# PG10__MCU.net
KiCad netlist of a schematic drawn in Altium Designer
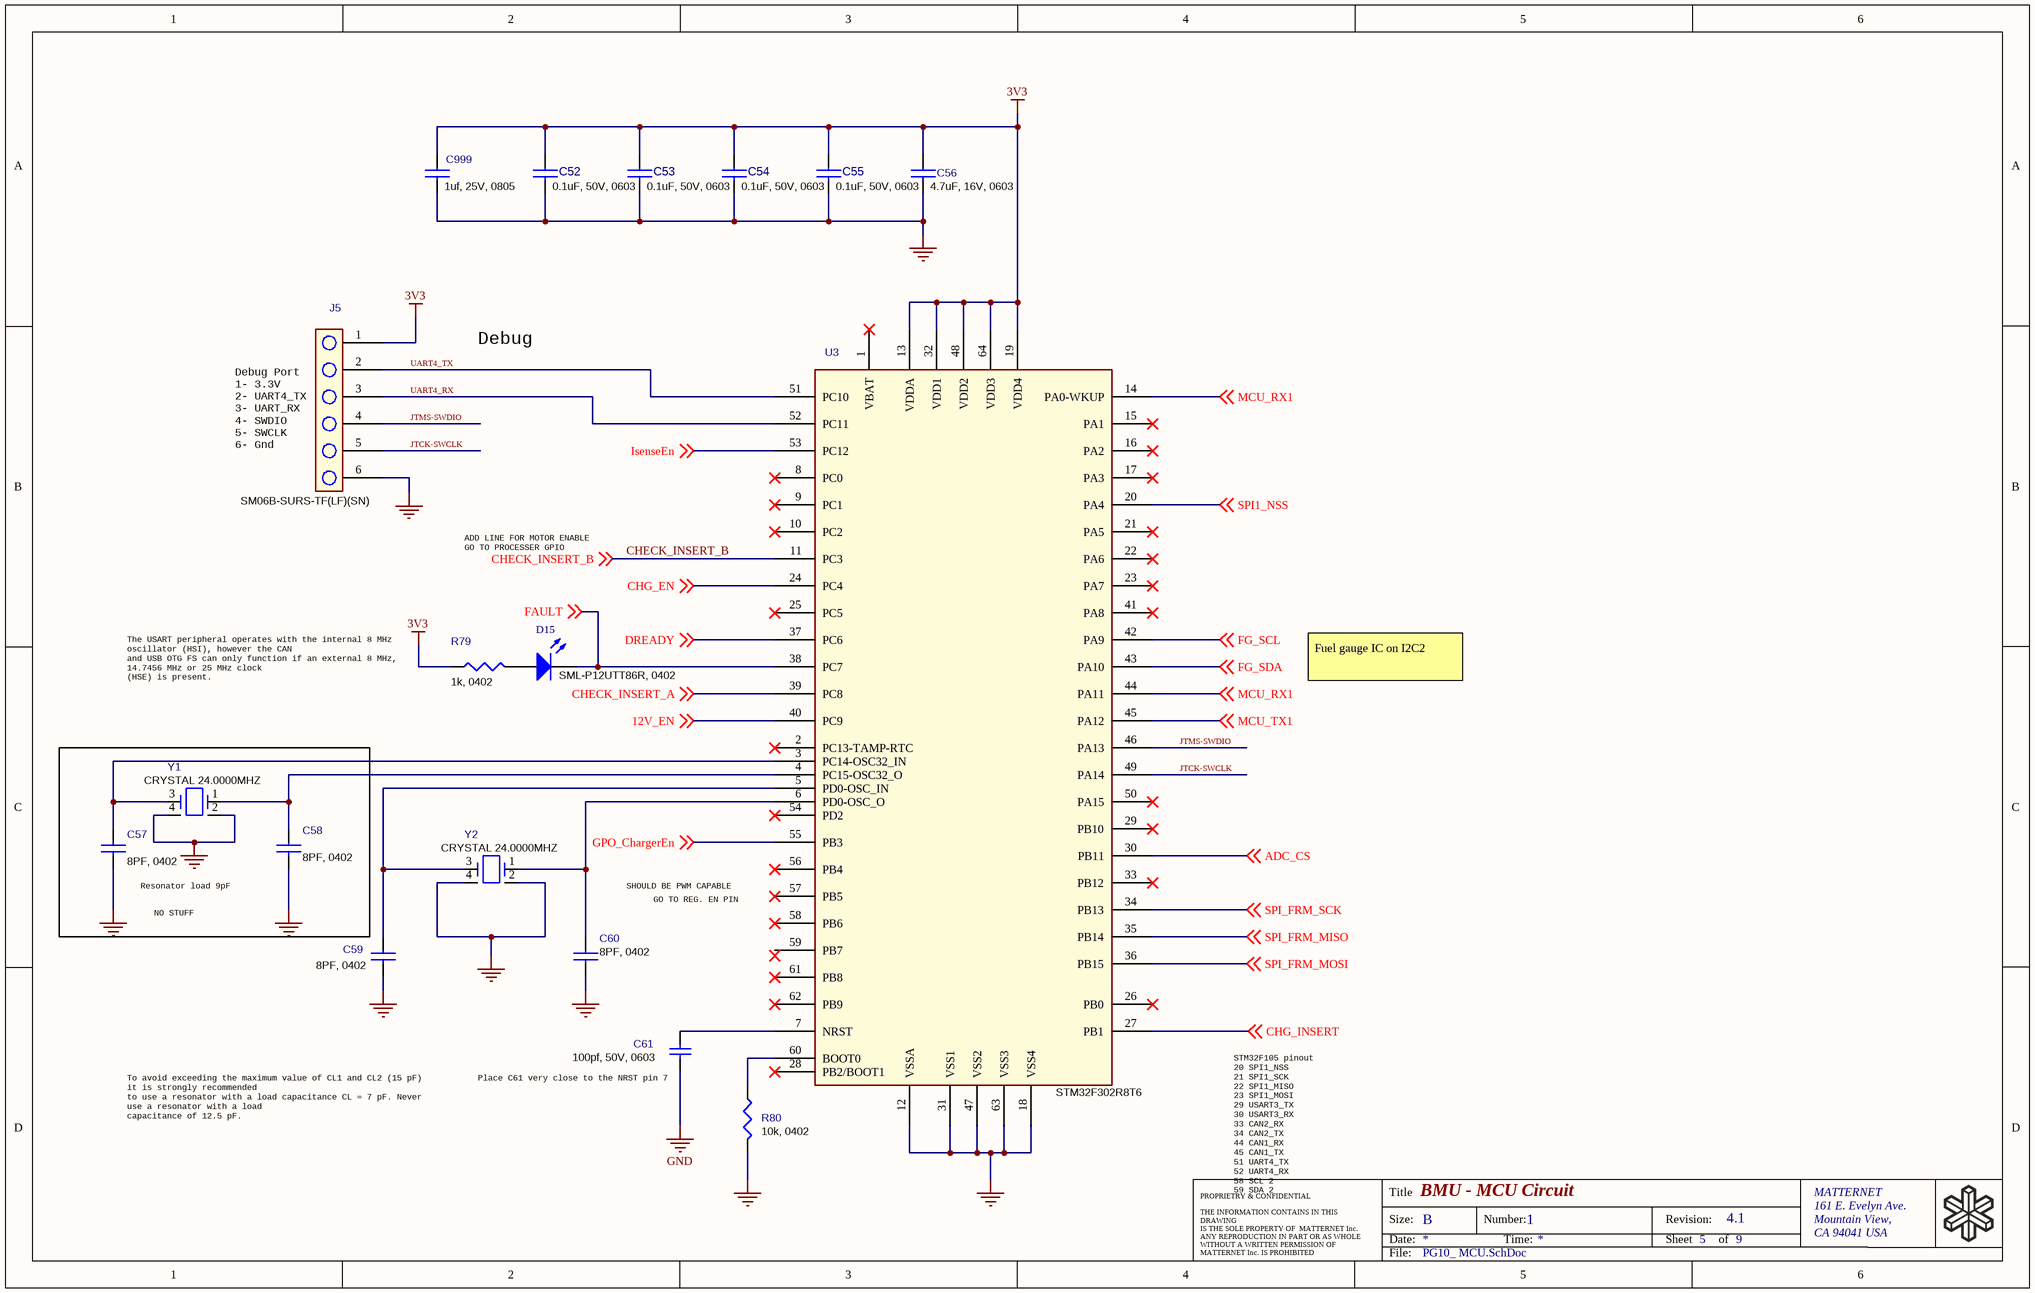
[diagram p0: PG10_ MCU.SchDoc]

(export (version "E")
  (design (tool "Eeschema 10.0.6"))
  (components
    (comp (ref "C52")
      (value "0.1uF, 50V, 0603")
      (footprint "C0603")
      (description "CAP CER 0.1UF 50V 10% X7R 0603")
      (fields
        (field (name "MANUFACTURER") "Murata")
        (field (name "MANUFACTURER PART NUMBER") "GCJ188R71E104KA12D")
      )
      (libsource (lib "*") (part "CAP-Generic-0603"))
    )
    (comp (ref "C53")
      (value "0.1uF, 50V, 0603")
      (footprint "C0603")
      (description "CAP CER 0.1UF 50V 10% X7R 0603")
      (fields
        (field (name "MANUFACTURER") "Murata")
        (field (name "MANUFACTURER PART NUMBER") "GCJ188R71E104KA12D")
      )
      (libsource (lib "*") (part "CAP-Generic-0603"))
    )
    (comp (ref "C54")
      (value "0.1uF, 50V, 0603")
      (footprint "C0603")
      (description "CAP CER 0.1UF 50V 10% X7R 0603")
      (fields
        (field (name "MANUFACTURER") "Murata")
        (field (name "MANUFACTURER PART NUMBER") "GCJ188R71E104KA12D")
      )
      (libsource (lib "*") (part "CAP-Generic-0603"))
    )
    (comp (ref "C55")
      (value "0.1uF, 50V, 0603")
      (footprint "C0603")
      (description "CAP CER 0.1UF 50V 10% X7R 0603")
      (fields
        (field (name "MANUFACTURER") "Murata")
        (field (name "MANUFACTURER PART NUMBER") "GCJ188R71E104KA12D")
      )
      (libsource (lib "*") (part "CAP-Generic-0603"))
    )
    (comp (ref "C56")
      (value "4.7uF, 16V, 0603")
      (footprint "C0805")
      (description "CAP CER 4.7UF 16V 10% X7R 0805")
      (fields
        (field (name "MANUFACTURER") "TDK")
        (field (name "MANUFACTURER PART NUMBER") "CGA4J3X7R1C475K125AE")
      )
      (libsource (lib "*") (part "CAP-Generic-0603"))
    )
    (comp (ref "C57")
      (value "8PF, 0402")
      (footprint "C0402")
      (description "CAP CER 8PF 50V C0G 0402")
      (fields
        (field (name "MANUFACTURER") "TDK")
        (field (name "MANUFACTURER PART NUMBER") "CGA2B2C0G1H080D050BA")
      )
      (libsource (lib "*") (part "CAP-Generic-0402"))
    )
    (comp (ref "C58")
      (value "8PF, 0402")
      (footprint "C0402")
      (description "CAP CER 8PF 50V C0G 0402")
      (fields
        (field (name "MANUFACTURER") "TDK")
        (field (name "MANUFACTURER PART NUMBER") "CGA2B2C0G1H080D050BA")
      )
      (libsource (lib "*") (part "CAP-Generic-0402"))
    )
    (comp (ref "C59")
      (value "8PF, 0402")
      (footprint "C0402")
      (description "CAP CER 8PF 50V C0G 0402")
      (fields
        (field (name "MANUFACTURER") "TDK")
        (field (name "MANUFACTURER PART NUMBER") "CGA2B2C0G1H080D050BA")
      )
      (libsource (lib "*") (part "CAP-Generic-0402"))
    )
    (comp (ref "C60")
      (value "8PF, 0402")
      (footprint "C0402")
      (description "CAP CER 8PF 50V C0G 0402")
      (fields
        (field (name "MANUFACTURER") "TDK")
        (field (name "MANUFACTURER PART NUMBER") "CGA2B2C0G1H080D050BA")
      )
      (libsource (lib "*") (part "CAP-Generic-0402"))
    )
    (comp (ref "C61")
      (value "100pf, 50V, 0603")
      (footprint "C0603")
      (description "CAP CER 100PF 50V NP0 0603")
      (fields
        (field (name "MANUFACTURER") "TDK")
        (field (name "MANUFACTURER PART NUMBER") "CGA3E2C0G1H101J080AE")
      )
      (libsource (lib "Miscellaneous Devices") (part "Cap"))
    )
    (comp (ref "C999")
      (value "1uf, 25V, 0805")
      (footprint "C0805")
      (description "CAP CER 1UF 25V X7R 0805")
      (fields
        (field (name "MANUFACTURER") "Murata")
        (field (name "MANUFACTURER PART NUMBER") "GCJ21BR71E105KA12L")
      )
      (libsource (lib "*") (part "CAP-Generic-0402"))
    )
    (comp (ref "D15")
      (value "SML-P12UTT86R, 0402")
      (footprint "D0402_1")
      (description "LED Uni-Color Red Chip LED 2-Pin 0402 T/R")
      (fields (field (name "MANUFACTURER") "Rohm") (field (name "MANUFACTURER PART NUMBER") "SML-P12U2TT86R"))
      (libsource (lib "Miscellaneous Devices") (part "LED0"))
    )
    (comp (ref "J5")
      (value "SM06B-SURS-TF(LF)(SN)")
      (footprint "0.8mm")
      (description "Headers & Wire Housings 6P SR UNSHRD HRD TIN OVER NI")
      (fields (field (name "MANUFACTURER") "JST"))
      (libsource (lib "*") (part "CONN-GENERIC-1X6"))
    )
    (comp (ref "R79")
      (value "1k, 0402")
      (footprint "R0402")
      (description "RES SMD 1K OHM 5% 1/16W 0402")
      (fields
        (field (name "MANUFACTURER") "Yageo")
        (field (name "MANUFACTURER PART NUMBER") "RC0402JR-071KL")
      )
      (libsource (lib "*") (part "R-Generic-0402"))
    )
    (comp (ref "R80")
      (value "10k, 0402")
      (footprint "R0402")
      (description "RES SMD 10K OHM 1% 1/16W 0402")
      (fields
        (field (name "MANUFACTURER") "Vishay Dale")
        (field (name "MANUFACTURER PART NUMBER") "CRCW040210K0FKTD")
      )
      (libsource (lib "Miscellaneous Devices") (part "R-Generic-0402"))
    )
    (comp (ref "U3")
      (value "STM32F302R8T6")
      (footprint "64LQFP")
      (description "MCU 32-bit STM32 ARM Cortex M4 RISC 128KB Flash 2.5V/3.3V 64-Pin LQFP Tray")
      (libsource (lib "*") (part "MCU-STM32F105RBT6-700-443"))
    )
    (comp (ref "Y1")
      (value "CRYSTAL 24.0000MHZ")
      (footprint "CRYSTAL_NX3225SA")
      (description "CRYSTAL 24.0000MHZ 8PF SMD")
      (fields
        (field (name "MANUFACTURER") "NDK")
        (field (name "MANUFACTURER PART NUMBER") "NX3225SA-24.000MHZ-STD-CSR-1")
      )
      (libsource (lib "*") (part "CRY-Generic"))
    )
    (comp (ref "Y2")
      (value "CRYSTAL 24.0000MHZ")
      (footprint "CRYSTAL_NX3225SA")
      (description "CRYSTAL 24.0000MHZ 8PF SMD")
      (fields
        (field (name "MANUFACTURER") "NDK")
        (field (name "MANUFACTURER PART NUMBER") "NX3225SA-24.000MHZ-STD-CSR-1")
      )
      (libsource (lib "*") (part "CRY-Generic"))
    )
  )
  (nets
    (net (code "1") (name "/JTCK-SWCLK") (class "Default")
      (node (ref "J5") (pin "5") (pinfunction "5_5") (pintype "passive"))
      (node (ref "U3") (pin "49") (pinfunction "PA14_49") (pintype "passive"))
    )
    (net (code "2") (name "/JTMS-SWDIO") (class "Default")
      (node (ref "J5") (pin "4") (pinfunction "4_4") (pintype "passive"))
      (node (ref "U3") (pin "46") (pinfunction "PA13_46") (pintype "passive"))
    )
    (net (code "3") (name "/UART4_RX") (class "Default")
      (node (ref "J5") (pin "3") (pinfunction "3_3") (pintype "passive"))
      (node (ref "U3") (pin "52") (pinfunction "PC11_52") (pintype "passive"))
    )
    (net (code "4") (name "/UART4_TX") (class "Default")
      (node (ref "J5") (pin "2") (pinfunction "2_2") (pintype "passive"))
      (node (ref "U3") (pin "51") (pinfunction "PC10_51") (pintype "passive"))
    )
    (net (code "5") (name "3V3") (class "Default")
      (node (ref "C52") (pin "1") (pinfunction "1_1") (pintype "passive"))
      (node (ref "C53") (pin "1") (pinfunction "1_1") (pintype "passive"))
      (node (ref "C54") (pin "1") (pinfunction "1_1") (pintype "passive"))
      (node (ref "C55") (pin "1") (pinfunction "1_1") (pintype "passive"))
      (node (ref "C56") (pin "1") (pinfunction "1_1") (pintype "passive"))
      (node (ref "C999") (pin "1") (pinfunction "1_1") (pintype "passive"))
      (node (ref "J5") (pin "1") (pinfunction "1_1") (pintype "passive"))
      (node (ref "R79") (pin "1") (pinfunction "1_1") (pintype "passive"))
      (node (ref "U3") (pin "13") (pinfunction "VDDA_13") (pintype "passive"))
      (node (ref "U3") (pin "19") (pinfunction "VDD4_19") (pintype "passive"))
      (node (ref "U3") (pin "32") (pinfunction "VDD1_32") (pintype "passive"))
      (node (ref "U3") (pin "48") (pinfunction "VDD2_48") (pintype "passive"))
      (node (ref "U3") (pin "64") (pinfunction "VDD3_64") (pintype "passive"))
    )
    (net (code "6") (name "12V_EN") (class "Default")
      (node (ref "U3") (pin "40") (pinfunction "PC9_40") (pintype "passive"))
    )
    (net (code "7") (name "ADC_CS") (class "Default")
      (node (ref "U3") (pin "30") (pinfunction "PB11_30") (pintype "passive"))
    )
    (net (code "8") (name "CHECK_INSERT_A") (class "Default")
      (node (ref "U3") (pin "39") (pinfunction "PC8_39") (pintype "passive"))
    )
    (net (code "9") (name "CHECK_INSERT_B") (class "Default")
      (node (ref "U3") (pin "11") (pinfunction "PC3_11") (pintype "passive"))
    )
    (net (code "10") (name "CHG_EN") (class "Default")
      (node (ref "U3") (pin "24") (pinfunction "PC4_24") (pintype "passive"))
    )
    (net (code "11") (name "CHG_INSERT") (class "Default")
      (node (ref "U3") (pin "27") (pinfunction "PB1_27") (pintype "passive"))
    )
    (net (code "12") (name "DREADY") (class "Default")
      (node (ref "U3") (pin "37") (pinfunction "PC6_37") (pintype "passive"))
    )
    (net (code "13") (name "FAULT") (class "Default")
      (node (ref "D15") (pin "2") (pinfunction "K_2") (pintype "passive"))
      (node (ref "U3") (pin "38") (pinfunction "PC7_38") (pintype "passive"))
    )
    (net (code "14") (name "FG_SCL") (class "Default")
      (node (ref "U3") (pin "42") (pinfunction "PA9_42") (pintype "passive"))
    )
    (net (code "15") (name "FG_SDA") (class "Default")
      (node (ref "U3") (pin "43") (pinfunction "PA10_43") (pintype "passive"))
    )
    (net (code "16") (name "GND") (class "Default")
      (node (ref "C52") (pin "2") (pinfunction "2_2") (pintype "passive"))
      (node (ref "C53") (pin "2") (pinfunction "2_2") (pintype "passive"))
      (node (ref "C54") (pin "2") (pinfunction "2_2") (pintype "passive"))
      (node (ref "C55") (pin "2") (pinfunction "2_2") (pintype "passive"))
      (node (ref "C56") (pin "2") (pinfunction "2_2") (pintype "passive"))
      (node (ref "C57") (pin "2") (pinfunction "2_2") (pintype "passive"))
      (node (ref "C58") (pin "2") (pinfunction "2_2") (pintype "passive"))
      (node (ref "C59") (pin "2") (pinfunction "2_2") (pintype "passive"))
      (node (ref "C60") (pin "2") (pinfunction "2_2") (pintype "passive"))
      (node (ref "C61") (pin "1") (pinfunction "1_1") (pintype "passive"))
      (node (ref "C999") (pin "2") (pinfunction "2_2") (pintype "passive"))
      (node (ref "J5") (pin "6") (pinfunction "6_6") (pintype "passive"))
      (node (ref "R80") (pin "2") (pinfunction "2_2") (pintype "passive"))
      (node (ref "U3") (pin "12") (pinfunction "VSSA_12") (pintype "passive"))
      (node (ref "U3") (pin "18") (pinfunction "VSS4_18") (pintype "passive"))
      (node (ref "U3") (pin "31") (pinfunction "VSS1_31") (pintype "passive"))
      (node (ref "U3") (pin "47") (pinfunction "VSS2_47") (pintype "passive"))
      (node (ref "U3") (pin "63") (pinfunction "VSS3_63") (pintype "passive"))
      (node (ref "Y1") (pin "2") (pinfunction "2_2") (pintype "passive"))
      (node (ref "Y1") (pin "4") (pinfunction "4_4") (pintype "passive"))
      (node (ref "Y2") (pin "2") (pinfunction "2_2") (pintype "passive"))
      (node (ref "Y2") (pin "4") (pinfunction "4_4") (pintype "passive"))
    )
    (net (code "17") (name "GPO_ChargerEn") (class "Default")
      (node (ref "U3") (pin "55") (pinfunction "PB3_55") (pintype "passive"))
    )
    (net (code "18") (name "IsenseEn") (class "Default")
      (node (ref "U3") (pin "53") (pinfunction "PC12_53") (pintype "passive"))
    )
    (net (code "19") (name "MCU_RX1") (class "Default")
      (node (ref "U3") (pin "14") (pinfunction "PA0-WKUP_14") (pintype "passive"))
      (node (ref "U3") (pin "44") (pinfunction "PA11_44") (pintype "passive"))
    )
    (net (code "20") (name "MCU_TX1") (class "Default")
      (node (ref "U3") (pin "45") (pinfunction "PA12_45") (pintype "passive"))
    )
    (net (code "21") (name "Net-(U3-BOOT0)") (class "Default")
      (node (ref "R80") (pin "1") (pinfunction "1_1") (pintype "passive"))
      (node (ref "U3") (pin "60") (pinfunction "BOOT0_60") (pintype "passive"))
    )
    (net (code "22") (name "Net-(U3-NRST)") (class "Default")
      (node (ref "C61") (pin "2") (pinfunction "2_2") (pintype "passive"))
      (node (ref "U3") (pin "7") (pinfunction "NRST_7") (pintype "passive"))
    )
    (net (code "23") (name "Net-(U3-PC14-OSC32_IN)") (class "Default")
      (node (ref "C57") (pin "1") (pinfunction "1_1") (pintype "passive"))
      (node (ref "U3") (pin "3") (pinfunction "PC14-OSC32_IN_3") (pintype "passive"))
      (node (ref "Y1") (pin "3") (pinfunction "3_3") (pintype "passive"))
    )
    (net (code "24") (name "Net-(U3-PC15-OSC32_O)") (class "Default")
      (node (ref "C58") (pin "1") (pinfunction "1_1") (pintype "passive"))
      (node (ref "U3") (pin "4") (pinfunction "PC15-OSC32_O_4") (pintype "passive"))
      (node (ref "Y1") (pin "1") (pinfunction "1_1") (pintype "passive"))
    )
    (net (code "25") (name "Net-(U3-PD0-OSC_IN)") (class "Default")
      (node (ref "C59") (pin "1") (pinfunction "1_1") (pintype "passive"))
      (node (ref "U3") (pin "5") (pinfunction "PD0-OSC_IN_5") (pintype "passive"))
      (node (ref "Y2") (pin "3") (pinfunction "3_3") (pintype "passive"))
    )
    (net (code "26") (name "Net-(U3-PD0-OSC_O)") (class "Default")
      (node (ref "C60") (pin "1") (pinfunction "1_1") (pintype "passive"))
      (node (ref "U3") (pin "6") (pinfunction "PD0-OSC_O_6") (pintype "passive"))
      (node (ref "Y2") (pin "1") (pinfunction "1_1") (pintype "passive"))
    )
    (net (code "27") (name "SPI1_NSS") (class "Default")
      (node (ref "U3") (pin "20") (pinfunction "PA4_20") (pintype "passive"))
    )
    (net (code "28") (name "SPI_FRM_MISO") (class "Default")
      (node (ref "U3") (pin "35") (pinfunction "PB14_35") (pintype "passive"))
    )
    (net (code "29") (name "SPI_FRM_MOSI") (class "Default")
      (node (ref "U3") (pin "36") (pinfunction "PB15_36") (pintype "passive"))
    )
    (net (code "30") (name "SPI_FRM_SCK") (class "Default")
      (node (ref "U3") (pin "34") (pinfunction "PB13_34") (pintype "passive"))
    )
    (net (code "31") (name "unconnected-(D15-A-Pad1)") (class "Default")
      (node (ref "D15") (pin "1") (pinfunction "A_1") (pintype "passive"))
    )
    (net (code "32") (name "unconnected-(R79-Pad2)") (class "Default")
      (node (ref "R79") (pin "2") (pinfunction "2_2") (pintype "passive"))
    )
    (net (code "33") (name "unconnected-(U3-PA1-Pad15)") (class "Default")
      (node (ref "U3") (pin "15") (pinfunction "PA1_15") (pintype "passive+no_connect"))
    )
    (net (code "34") (name "unconnected-(U3-PA2-Pad16)") (class "Default")
      (node (ref "U3") (pin "16") (pinfunction "PA2_16") (pintype "passive+no_connect"))
    )
    (net (code "35") (name "unconnected-(U3-PA3-Pad17)") (class "Default")
      (node (ref "U3") (pin "17") (pinfunction "PA3_17") (pintype "passive+no_connect"))
    )
    (net (code "36") (name "unconnected-(U3-PA5-Pad21)") (class "Default")
      (node (ref "U3") (pin "21") (pinfunction "PA5_21") (pintype "passive+no_connect"))
    )
    (net (code "37") (name "unconnected-(U3-PA6-Pad22)") (class "Default")
      (node (ref "U3") (pin "22") (pinfunction "PA6_22") (pintype "passive+no_connect"))
    )
    (net (code "38") (name "unconnected-(U3-PA7-Pad23)") (class "Default")
      (node (ref "U3") (pin "23") (pinfunction "PA7_23") (pintype "passive+no_connect"))
    )
    (net (code "39") (name "unconnected-(U3-PA8-Pad41)") (class "Default")
      (node (ref "U3") (pin "41") (pinfunction "PA8_41") (pintype "passive+no_connect"))
    )
    (net (code "40") (name "unconnected-(U3-PA15-Pad50)") (class "Default")
      (node (ref "U3") (pin "50") (pinfunction "PA15_50") (pintype "passive+no_connect"))
    )
    (net (code "41") (name "unconnected-(U3-PB0-Pad26)") (class "Default")
      (node (ref "U3") (pin "26") (pinfunction "PB0_26") (pintype "passive+no_connect"))
    )
    (net (code "42") (name "unconnected-(U3-PB2{slash}BOOT1-Pad28)") (class "Default")
      (node (ref "U3") (pin "28") (pinfunction "PB2/BOOT1_28") (pintype "passive+no_connect"))
    )
    (net (code "43") (name "unconnected-(U3-PB4-Pad56)") (class "Default")
      (node (ref "U3") (pin "56") (pinfunction "PB4_56") (pintype "passive+no_connect"))
    )
    (net (code "44") (name "unconnected-(U3-PB5-Pad57)") (class "Default")
      (node (ref "U3") (pin "57") (pinfunction "PB5_57") (pintype "passive+no_connect"))
    )
    (net (code "45") (name "unconnected-(U3-PB6-Pad58)") (class "Default")
      (node (ref "U3") (pin "58") (pinfunction "PB6_58") (pintype "passive+no_connect"))
    )
    (net (code "46") (name "unconnected-(U3-PB7-Pad59)") (class "Default")
      (node (ref "U3") (pin "59") (pinfunction "PB7_59") (pintype "passive"))
    )
    (net (code "47") (name "unconnected-(U3-PB8-Pad61)") (class "Default")
      (node (ref "U3") (pin "61") (pinfunction "PB8_61") (pintype "passive+no_connect"))
    )
    (net (code "48") (name "unconnected-(U3-PB9-Pad62)") (class "Default")
      (node (ref "U3") (pin "62") (pinfunction "PB9_62") (pintype "passive+no_connect"))
    )
    (net (code "49") (name "unconnected-(U3-PB10-Pad29)") (class "Default")
      (node (ref "U3") (pin "29") (pinfunction "PB10_29") (pintype "passive+no_connect"))
    )
    (net (code "50") (name "unconnected-(U3-PB12-Pad33)") (class "Default")
      (node (ref "U3") (pin "33") (pinfunction "PB12_33") (pintype "passive+no_connect"))
    )
    (net (code "51") (name "unconnected-(U3-PC0-Pad8)") (class "Default")
      (node (ref "U3") (pin "8") (pinfunction "PC0_8") (pintype "passive+no_connect"))
    )
    (net (code "52") (name "unconnected-(U3-PC1-Pad9)") (class "Default")
      (node (ref "U3") (pin "9") (pinfunction "PC1_9") (pintype "passive+no_connect"))
    )
    (net (code "53") (name "unconnected-(U3-PC2-Pad10)") (class "Default")
      (node (ref "U3") (pin "10") (pinfunction "PC2_10") (pintype "passive+no_connect"))
    )
    (net (code "54") (name "unconnected-(U3-PC5-Pad25)") (class "Default")
      (node (ref "U3") (pin "25") (pinfunction "PC5_25") (pintype "passive+no_connect"))
    )
    (net (code "55") (name "unconnected-(U3-PC13-TAMP-RTC-Pad2)") (class "Default")
      (node (ref "U3") (pin "2") (pinfunction "PC13-TAMP-RTC_2") (pintype "passive+no_connect"))
    )
    (net (code "56") (name "unconnected-(U3-PD2-Pad54)") (class "Default")
      (node (ref "U3") (pin "54") (pinfunction "PD2_54") (pintype "passive+no_connect"))
    )
    (net (code "57") (name "unconnected-(U3-VBAT-Pad1)") (class "Default")
      (node (ref "U3") (pin "1") (pinfunction "VBAT_1") (pintype "passive+no_connect"))
    )
  )
)
